# 5V_Buck.net
KiCad netlist of a schematic drawn in Altium Designer
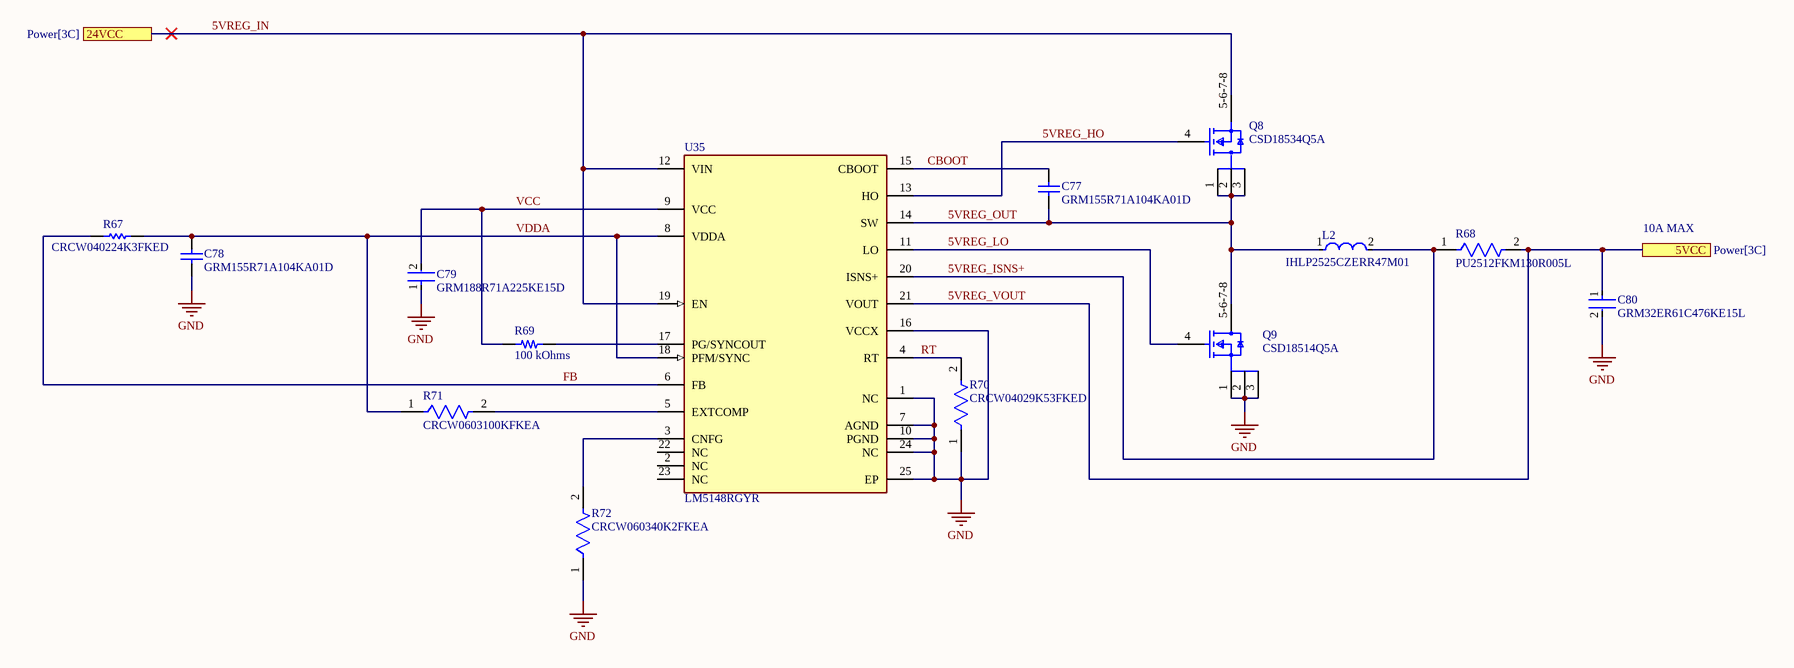
[diagram p0: 5V_Buck.SchDoc]

(export (version "E")
  (design (tool "Eeschema 10.0.6"))
  (components
    (comp (ref "C77")
      (value "GRM155R71A104KA01D")
      (footprint "CAPC1005X55X25LL05T10")
      (description "Chip Capacitor, 0.1 uF, +/- 10%, 10 V, -55 to 125 degC, 0402 (1005 Metric), RoHS, Tape and Reel")
      (fields (field (name "MANUFACTURER") "Murata"))
      (libsource (lib "Altium Content Vault") (part "CAP-NP-2"))
    )
    (comp (ref "C78")
      (value "GRM155R71A104KA01D")
      (footprint "CAPC1005X55X25LL05T10")
      (description "Chip Capacitor, 0.1 uF, +/- 10%, 10 V, -55 to 125 degC, 0402 (1005 Metric), RoHS, Tape and Reel")
      (fields (field (name "MANUFACTURER") "Murata"))
      (libsource (lib "Altium Content Vault") (part "CAP-NP-2"))
    )
    (comp (ref "C79")
      (value "GRM188R71A225KE15D")
      (footprint "FP-GRM188-0_1-e0_2_0_5-MFG")
      (description "Chip Multilayer Ceramic Capacitors for General Purpose, 0603, 2.2uF, X7R, 15%, 10%, 10V")
      (fields (field (name "VOLTAGE") "10V") (field (name "TOLERANCE") "10%"))
      (libsource (lib "Altium Content Vault") (part "11868f565c42a9108669ba33697ecf6"))
    )
    (comp (ref "C80")
      (value "GRM32ER61C476KE15L")
      (footprint "FP-GRM32E-0_3-0_2-IPC_C")
      (description "CAP CER 47UF 16V X5R 1210")
      (fields (field (name "VOLTAGE") "16V") (field (name "TOLERANCE") "10%"))
      (libsource (lib "Altium Content Vault") (part "b4654b650e69147ec39a6b967a45e02"))
    )
    (comp (ref "L2")
      (value "IHLP2525CZERR47M01")
      (footprint "FP-IHLP-2525CZ-FP_2_413x3-MFG")
      (description "Commercial Inductors, High Saturation Series 0.47uH 17.5A 4.2mΩ 20%")
      (fields (field (name "TOLERANCE") "20%"))
      (libsource (lib "Altium Content Vault") (part "725321dda6339637d4d059423bc1c3c"))
    )
    (comp (ref "Q8")
      (value "CSD18534Q5A")
      (footprint "FP-DQJ0008A-MFG")
      (description "MOSFET N-CH 60V 8SON")
      (fields
        (field (name "OCTOPART") "https://octopart.com/csd18534q5a-texas+instruments-22791040")
        (field (name "MANUFACTURER") "Texas Instruments")
      )
      (libsource (lib "Altium Content Vault") (part "2b493a92fcdc54dddf28a3aa2503ef1"))
    )
    (comp (ref "Q9")
      (value "CSD18514Q5A")
      (footprint "FP-DQJ0008A-MFG")
      (description "MOSFET N-CH 40V 89A 8VSON")
      (libsource (lib "Altium Content Vault") (part "e0baf4780622716b99a4fe4ad34e686"))
    )
    (comp (ref "R67")
      (value "CRCW040224K3FKED")
      (footprint "RESC1005X40X25LL05T05")
      (fields (field (name "MANUFACTURER") "Vishay Dale"))
      (libsource (lib "Altium Content Vault") (part "RES"))
    )
    (comp (ref "R68")
      (value "PU2512FKM130R005L")
      (footprint "FP-PU2512-0R005-MFG")
      (description "METAL SHUNT RESISTOR 2512 1% 75P")
      (fields
        (field (name "OCTOPART") "https://octopart.com/pu2512fkm130r005l-yageo-96774569")
        (field (name "TOLERANCE") "1%")
      )
      (libsource (lib "Altium Content Vault") (part "1029c3af85768c4190bb7ad29bc67b5"))
    )
    (comp (ref "R69")
      (value "100 kOhms")
      (footprint "RES 0603_1608")
      (description "RES SMD 100K OHM 1% 1/10W 0603")
      (fields (field (name "PART NUMBER") "AA0603FR-07100KL") (field (name "MANUFACTURER") "Yageo"))
      (libsource (lib "altium_library") (part "Resistor"))
    )
    (comp (ref "R70")
      (value "CRCW04029K53FKED")
      (footprint "FP-CRCW0402-e3-MFG")
      (description "RES Thick Film, 9.53kΩ, 1%, 0.063W, 100ppm/°C, 0402")
      (fields (field (name "TOLERANCE") "1%"))
      (libsource (lib "Altium Content Vault") (part "1029c3af85768c4190bb7ad29bc67b5"))
    )
    (comp (ref "R71")
      (value "CRCW0603100KFKEA")
      (footprint "FP-CRCW0603-e3-IPC_C")
      (description "RES Thick Film, 100kΩ, 1%, 0.1W, 100ppm/°C, 0603")
      (fields (field (name "TOLERANCE") "1%"))
      (libsource (lib "Altium Content Vault") (part "1029c3af85768c4190bb7ad29bc67b5"))
    )
    (comp (ref "R72")
      (value "CRCW060340K2FKEA")
      (footprint "FP-CRCW0603-e3-IPC_B")
      (description "RES Thick Film, 40.2kΩ, 1%, 0.1W, 100ppm/°C, 0603")
      (fields (field (name "TOLERANCE") "1%"))
      (libsource (lib "Altium Content Vault") (part "1029c3af85768c4190bb7ad29bc67b5"))
    )
    (comp (ref "U35")
      (value "LM5148RGYR")
      (footprint "FP-RGY0024F-MFG")
      (description "LM5148RGYR 3.5-V to 80-V, current mode synchronous buck controller 24-VQFN -40 to 125")
      (libsource (lib "Altium Content Vault") (part "ab60acdb83b3e8c6cb53feaa4ccc0a4"))
    )
  )
  (nets
    (net (code "1") (name "/5VREG_HO") (class "Default")
      (node (ref "Q8") (pin "4") (pinfunction "G_4") (pintype "passive"))
      (node (ref "U35") (pin "13") (pinfunction "HO_13") (pintype "passive"))
    )
    (net (code "2") (name "/5VREG_IN") (class "Default")
      (node (ref "Q8") (pin "5-6-7-8") (pinfunction "D_5-6-7-8") (pintype "passive"))
      (node (ref "U35") (pin "12") (pinfunction "VIN_12") (pintype "power_in"))
      (node (ref "U35") (pin "19") (pinfunction "EN_19") (pintype "input"))
    )
    (net (code "3") (name "/5VREG_ISNS+") (class "Default")
      (node (ref "L2") (pin "2") (pinfunction "2_2") (pintype "passive"))
      (node (ref "R68") (pin "1") (pinfunction "1_1") (pintype "passive"))
      (node (ref "U35") (pin "20") (pinfunction "ISNS+_20") (pintype "passive"))
    )
    (net (code "4") (name "/5VREG_LO") (class "Default")
      (node (ref "Q9") (pin "4") (pinfunction "G_4") (pintype "passive"))
      (node (ref "U35") (pin "11") (pinfunction "LO_11") (pintype "passive"))
    )
    (net (code "5") (name "/5VREG_OUT") (class "Default")
      (node (ref "C77") (pin "1") (pinfunction "1_1") (pintype "passive"))
      (node (ref "L2") (pin "1") (pinfunction "1_1") (pintype "passive"))
      (node (ref "Q8") (pin "1") (pinfunction "S_1") (pintype "passive"))
      (node (ref "Q8") (pin "2") (pinfunction "S_2") (pintype "passive"))
      (node (ref "Q8") (pin "3") (pinfunction "S_3") (pintype "passive"))
      (node (ref "Q9") (pin "5-6-7-8") (pinfunction "D_5-6-7-8") (pintype "passive"))
      (node (ref "U35") (pin "14") (pinfunction "SW_14") (pintype "power_in"))
    )
    (net (code "6") (name "/5VREG_VOUT") (class "Default")
      (node (ref "C80") (pin "1") (pinfunction "1_1") (pintype "passive"))
      (node (ref "R68") (pin "2") (pinfunction "2_2") (pintype "passive"))
      (node (ref "U35") (pin "21") (pinfunction "VOUT_21") (pintype "passive"))
    )
    (net (code "7") (name "/CBOOT") (class "Default")
      (node (ref "C77") (pin "2") (pinfunction "2_2") (pintype "passive"))
      (node (ref "U35") (pin "15") (pinfunction "CBOOT_15") (pintype "power_in"))
    )
    (net (code "8") (name "/FB") (class "Default")
      (node (ref "R67") (pin "1") (pinfunction "1_1") (pintype "passive"))
      (node (ref "U35") (pin "6") (pinfunction "FB_6") (pintype "passive"))
    )
    (net (code "9") (name "/RT") (class "Default")
      (node (ref "R70") (pin "2") (pinfunction "2_2") (pintype "passive"))
      (node (ref "U35") (pin "4") (pinfunction "RT_4") (pintype "passive"))
    )
    (net (code "10") (name "/VCC") (class "Default")
      (node (ref "C79") (pin "2") (pinfunction "2_2") (pintype "passive"))
      (node (ref "R69") (pin "1") (pinfunction "1_1") (pintype "passive"))
      (node (ref "U35") (pin "9") (pinfunction "VCC_9") (pintype "power_in"))
    )
    (net (code "11") (name "/VDDA") (class "Default")
      (node (ref "C78") (pin "2") (pinfunction "2_2") (pintype "passive"))
      (node (ref "R67") (pin "2") (pinfunction "2_2") (pintype "passive"))
      (node (ref "R71") (pin "1") (pinfunction "1_1") (pintype "passive"))
      (node (ref "U35") (pin "18") (pinfunction "PFM/SYNC_18") (pintype "input"))
      (node (ref "U35") (pin "8") (pinfunction "VDDA_8") (pintype "passive"))
    )
    (net (code "12") (name "GND") (class "Default")
      (node (ref "C78") (pin "1") (pinfunction "1_1") (pintype "passive"))
      (node (ref "C79") (pin "1") (pinfunction "1_1") (pintype "passive"))
      (node (ref "C80") (pin "2") (pinfunction "2_2") (pintype "passive"))
      (node (ref "Q9") (pin "1") (pinfunction "S_1") (pintype "passive"))
      (node (ref "Q9") (pin "2") (pinfunction "S_2") (pintype "passive"))
      (node (ref "Q9") (pin "3") (pinfunction "S_3") (pintype "passive"))
      (node (ref "R70") (pin "1") (pinfunction "1_1") (pintype "passive"))
      (node (ref "R72") (pin "1") (pinfunction "1_1") (pintype "passive"))
      (node (ref "U35") (pin "1") (pinfunction "NC_1") (pintype "passive"))
      (node (ref "U35") (pin "10") (pinfunction "PGND_10") (pintype "power_in"))
      (node (ref "U35") (pin "16") (pinfunction "VCCX_16") (pintype "power_in"))
      (node (ref "U35") (pin "24") (pinfunction "NC_24") (pintype "passive"))
      (node (ref "U35") (pin "25") (pinfunction "EP_25") (pintype "passive"))
      (node (ref "U35") (pin "7") (pinfunction "AGND_7") (pintype "power_in"))
    )
    (net (code "13") (name "Net-(U35-CNFG)") (class "Default")
      (node (ref "R72") (pin "2") (pinfunction "2_2") (pintype "passive"))
      (node (ref "U35") (pin "3") (pinfunction "CNFG_3") (pintype "passive"))
    )
    (net (code "14") (name "Net-(U35-EXTCOMP)") (class "Default")
      (node (ref "R71") (pin "2") (pinfunction "2_2") (pintype "passive"))
      (node (ref "U35") (pin "5") (pinfunction "EXTCOMP_5") (pintype "passive"))
    )
    (net (code "15") (name "Net-(U35-PG{slash}SYNCOUT)") (class "Default")
      (node (ref "R69") (pin "2") (pinfunction "2_2") (pintype "passive"))
      (node (ref "U35") (pin "17") (pinfunction "PG/SYNCOUT_17") (pintype "open_collector"))
    )
    (net (code "16") (name "unconnected-(U35-NC-Pad2)") (class "Default")
      (node (ref "U35") (pin "2") (pinfunction "NC_2") (pintype "passive"))
    )
    (net (code "17") (name "unconnected-(U35-NC-Pad22)") (class "Default")
      (node (ref "U35") (pin "22") (pinfunction "NC_22") (pintype "passive"))
    )
    (net (code "18") (name "unconnected-(U35-NC-Pad23)") (class "Default")
      (node (ref "U35") (pin "23") (pinfunction "NC_23") (pintype "passive"))
    )
  )
)
